# untitled.net
KiCad netlist of a schematic drawn in EAGLE
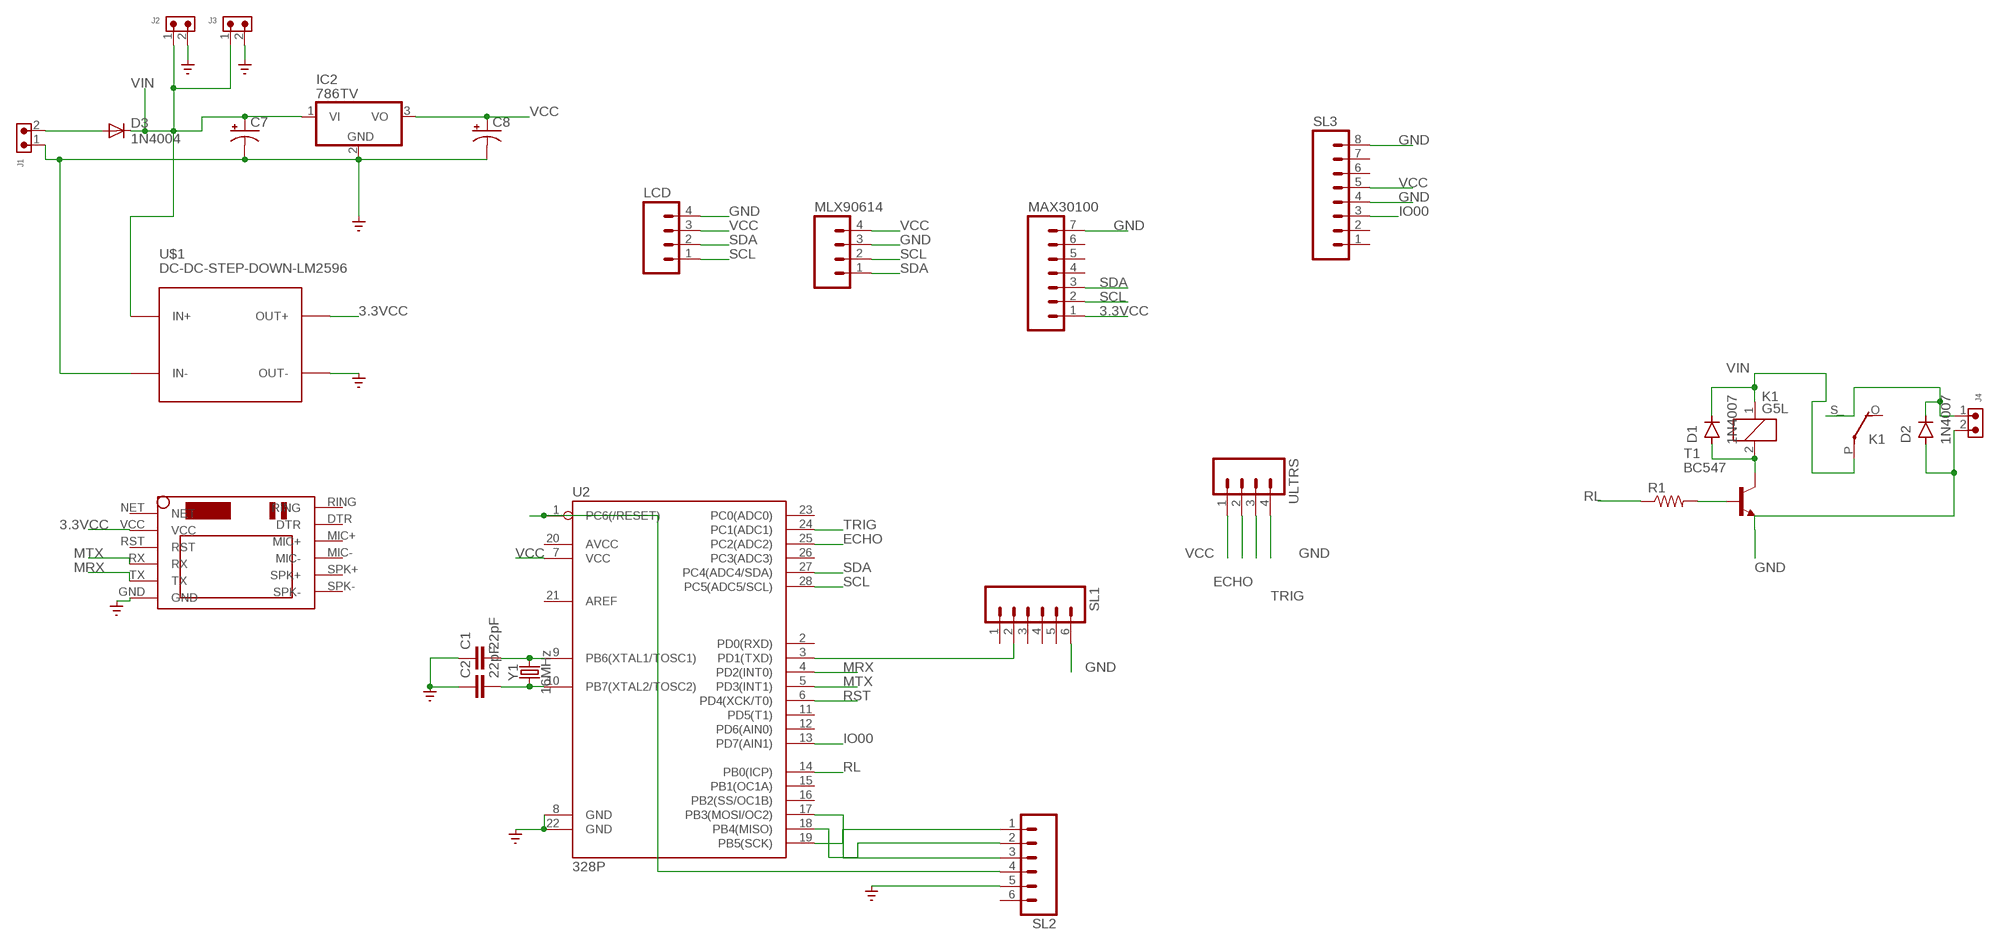
[diagram p0: schematic, sheet 1]

(export (version "E")
  (design (tool "Eeschema 10.0.6"))
  (components
    (comp (ref "C1")
      (value "22pF")
      (footprint "eagle-import:CAP-PTH-2.54")
      (libsource (lib "eagle-import") (part "22PF-PTH-2.54MM-200V-5%"))
    )
    (comp (ref "C2")
      (value "22pF")
      (footprint "eagle-import:CAP-PTH-2.54")
      (libsource (lib "eagle-import") (part "22PF-PTH-2.54MM-200V-5%"))
    )
    (comp (ref "C7")
      (value "CAPACITOR-PE5-10.5")
      (footprint "eagle-import:E5-10,5")
      (libsource (lib "eagle-import") (part "CAPACITOR-PE5-10.5"))
    )
    (comp (ref "C8")
      (value "CAPACITOR-PE5-6")
      (footprint "eagle-import:E5-6")
      (libsource (lib "eagle-import") (part "CAPACITOR-PE5-6"))
    )
    (comp (ref "D1")
      (value "1N4007")
      (footprint "eagle-import:DO-41")
      (fields
        (field (name "DIGIKEY_PART_NUMBER") "1N4007MSCT-ND")
        (field (name "MANUFACTURER") "Micro Commercial Co")
        (field (name "CREATED_BY") "PCBLayout.com")
      )
      (libsource (lib "eagle-import") (part "1N4007"))
    )
    (comp (ref "D2")
      (value "1N4007")
      (footprint "eagle-import:DO-41")
      (fields
        (field (name "DIGIKEY_PART_NUMBER") "1N4007MSCT-ND")
        (field (name "MANUFACTURER") "Micro Commercial Co")
        (field (name "CREATED_BY") "PCBLayout.com")
      )
      (libsource (lib "eagle-import") (part "1N4007"))
    )
    (comp (ref "D3")
      (value "1N4004")
      (footprint "eagle-import:DO41-10")
      (libsource (lib "eagle-import") (part "1N4004"))
    )
    (comp (ref "IC2")
      (value "786TV")
      (footprint "eagle-import:TO220V")
      (libsource (lib "eagle-import") (part "78TV6"))
    )
    (comp (ref "J1")
      (value "691305530002")
      (footprint "eagle-import:691305530002")
      (libsource (lib "eagle-import") (part "691305530002"))
    )
    (comp (ref "J2")
      (value "691305530002")
      (footprint "eagle-import:691305530002")
      (libsource (lib "eagle-import") (part "691305530002"))
    )
    (comp (ref "J3")
      (value "691305530002")
      (footprint "eagle-import:691305530002")
      (libsource (lib "eagle-import") (part "691305530002"))
    )
    (comp (ref "J4")
      (value "691305530002")
      (footprint "eagle-import:691305530002")
      (libsource (lib "eagle-import") (part "691305530002"))
    )
    (comp (ref "K1")
      (value "G5L")
      (footprint "eagle-import:G5LE")
      (libsource (lib "eagle-import") (part "G5L"))
    )
    (comp (ref "LCD")
      (value "M04")
      (footprint "eagle-import:04P")
      (libsource (lib "eagle-import") (part "M04"))
    )
    (comp (ref "MAX30100")
      (value "M07")
      (footprint "eagle-import:07P")
      (libsource (lib "eagle-import") (part "M07"))
    )
    (comp (ref "MLX90614")
      (value "M04")
      (footprint "eagle-import:04P")
      (libsource (lib "eagle-import") (part "M04"))
    )
    (comp (ref "R1")
      (value "R-US_0207/15")
      (footprint "eagle-import:0207_15")
      (libsource (lib "eagle-import") (part "R-US_0207/15"))
    )
    (comp (ref "SL1")
      (value "M06")
      (footprint "eagle-import:06P")
      (libsource (lib "eagle-import") (part "M06"))
    )
    (comp (ref "SL2")
      (value "M06")
      (footprint "eagle-import:06P")
      (libsource (lib "eagle-import") (part "M06"))
    )
    (comp (ref "SL3")
      (value "M08")
      (footprint "eagle-import:08P")
      (libsource (lib "eagle-import") (part "M08"))
    )
    (comp (ref "T1")
      (value "BC547")
      (footprint "eagle-import:TO92")
      (libsource (lib "eagle-import") (part "BC547"))
    )
    (comp (ref "U$1")
      (value "DC-DC-STEP-DOWN-LM2596")
      (footprint "eagle-import:DC-DC-STEP-DOWN-LM2596")
      (libsource (lib "eagle-import") (part "DC-DC-STEP-DOWN-LM2596"))
    )
    (comp (ref "U$2")
      (value "SIM800LMODULE")
      (footprint "eagle-import:SIM800LMODULE")
      (libsource (lib "eagle-import") (part "SIM800LMODULE"))
    )
    (comp (ref "U2")
      (value "328P")
      (footprint "eagle-import:DIP28")
      (libsource (lib "eagle-import") (part "ATMEGA328P_PDIP"))
    )
    (comp (ref "ULTRS")
      (value "M04")
      (footprint "eagle-import:04P")
      (libsource (lib "eagle-import") (part "M04"))
    )
    (comp (ref "Y1")
      (value "16MHz")
      (footprint "eagle-import:HC49US")
      (libsource (lib "eagle-import") (part "CRYSTAL-16MHZPTH-HC49US"))
    )
  )
  (nets
    (net (code "1") (name "/3.3VCC") (class "Default")
      (node (ref "MAX30100") (pin "1") (pinfunction "1_1") (pintype "passive"))
      (node (ref "U$1") (pin "OUT+") (pinfunction "OUT+_OUT+") (pintype "bidirectional"))
      (node (ref "U$2") (pin "VCC") (pinfunction "VCC_VCC") (pintype "bidirectional"))
    )
    (net (code "2") (name "/ECHO") (class "Default")
      (node (ref "U2") (pin "25") (pinfunction "PC2(ADC2)_25") (pintype "bidirectional"))
      (node (ref "ULTRS") (pin "2") (pinfunction "2_2") (pintype "passive"))
    )
    (net (code "3") (name "/IO00") (class "Default")
      (node (ref "SL3") (pin "3") (pinfunction "3_3") (pintype "passive"))
      (node (ref "U2") (pin "13") (pinfunction "PD7(AIN1)_13") (pintype "bidirectional"))
    )
    (net (code "4") (name "/MRX") (class "Default")
      (node (ref "U$2") (pin "TX") (pinfunction "TX_TX") (pintype "bidirectional"))
      (node (ref "U2") (pin "4") (pinfunction "PD2(INT0)_4") (pintype "bidirectional"))
    )
    (net (code "5") (name "/MTX") (class "Default")
      (node (ref "U$2") (pin "RX") (pinfunction "RX_RX") (pintype "bidirectional"))
      (node (ref "U2") (pin "5") (pinfunction "PD3(INT1)_5") (pintype "bidirectional"))
    )
    (net (code "6") (name "/RL") (class "Default")
      (node (ref "R1") (pin "1") (pinfunction "1_1") (pintype "passive"))
      (node (ref "U2") (pin "14") (pinfunction "PB0(ICP)_14") (pintype "bidirectional"))
    )
    (net (code "7") (name "/RST") (class "Default")
      (node (ref "U2") (pin "6") (pinfunction "PD4(XCK/T0)_6") (pintype "bidirectional"))
    )
    (net (code "8") (name "/SCL") (class "Default")
      (node (ref "LCD") (pin "1") (pinfunction "1_1") (pintype "passive"))
      (node (ref "MAX30100") (pin "2") (pinfunction "2_2") (pintype "passive"))
      (node (ref "MLX90614") (pin "2") (pinfunction "2_2") (pintype "passive"))
      (node (ref "U2") (pin "28") (pinfunction "PC5(ADC5/SCL)_28") (pintype "bidirectional"))
    )
    (net (code "9") (name "/SDA") (class "Default")
      (node (ref "LCD") (pin "2") (pinfunction "2_2") (pintype "passive"))
      (node (ref "MAX30100") (pin "3") (pinfunction "3_3") (pintype "passive"))
      (node (ref "MLX90614") (pin "1") (pinfunction "1_1") (pintype "passive"))
      (node (ref "U2") (pin "27") (pinfunction "PC4(ADC4/SDA)_27") (pintype "bidirectional"))
    )
    (net (code "10") (name "/TRIG") (class "Default")
      (node (ref "U2") (pin "24") (pinfunction "PC1(ADC1)_24") (pintype "bidirectional"))
      (node (ref "ULTRS") (pin "3") (pinfunction "3_3") (pintype "passive"))
    )
    (net (code "11") (name "/VCC") (class "Default")
      (node (ref "C8") (pin "+") (pinfunction "+_+") (pintype "passive"))
      (node (ref "IC2") (pin "3") (pinfunction "VO_3") (pintype "passive"))
      (node (ref "LCD") (pin "3") (pinfunction "3_3") (pintype "passive"))
      (node (ref "MLX90614") (pin "4") (pinfunction "4_4") (pintype "passive"))
      (node (ref "SL3") (pin "5") (pinfunction "5_5") (pintype "passive"))
      (node (ref "U2") (pin "7") (pinfunction "VCC_7") (pintype "bidirectional"))
      (node (ref "ULTRS") (pin "1") (pinfunction "1_1") (pintype "passive"))
    )
    (net (code "12") (name "/VIN") (class "Default")
      (node (ref "C7") (pin "+") (pinfunction "+_+") (pintype "passive"))
      (node (ref "D1") (pin "C") (pinfunction "C_C") (pintype "passive"))
      (node (ref "D3") (pin "C") (pinfunction "C_C") (pintype "passive"))
      (node (ref "IC2") (pin "1") (pinfunction "VI_1") (pintype "input"))
      (node (ref "J2") (pin "1") (pinfunction "1_1") (pintype "passive"))
      (node (ref "J3") (pin "1") (pinfunction "1_1") (pintype "passive"))
      (node (ref "K1") (pin "1") (pinfunction "1_1") (pintype "passive"))
      (node (ref "K1") (pin "P") (pinfunction "P_P") (pintype "passive"))
      (node (ref "U$1") (pin "IN+") (pinfunction "IN+_IN+") (pintype "bidirectional"))
    )
    (net (code "13") (name "Net-(D2-PadC)") (class "Default")
      (node (ref "D2") (pin "C") (pinfunction "C_C") (pintype "passive"))
      (node (ref "J4") (pin "1") (pinfunction "1_1") (pintype "passive"))
      (node (ref "K1") (pin "S") (pinfunction "S_S") (pintype "passive"))
    )
    (net (code "14") (name "Net-(D3-PadA)") (class "Default")
      (node (ref "D3") (pin "A") (pinfunction "A_A") (pintype "passive"))
      (node (ref "J1") (pin "2") (pinfunction "2_2") (pintype "passive"))
    )
    (net (code "15") (name "Net-(T1-B)") (class "Default")
      (node (ref "R1") (pin "2") (pinfunction "2_2") (pintype "passive"))
      (node (ref "T1") (pin "2") (pinfunction "B_2") (pintype "passive"))
    )
    (net (code "16") (name "Net-(T1-C)") (class "Default")
      (node (ref "D1") (pin "A") (pinfunction "A_A") (pintype "passive"))
      (node (ref "K1") (pin "2") (pinfunction "2_2") (pintype "passive"))
      (node (ref "T1") (pin "3") (pinfunction "C_3") (pintype "passive"))
    )
    (net (code "17") (name "Net-(U2-PB3(MOSI{slash}OC2))") (class "Default")
      (node (ref "SL2") (pin "3") (pinfunction "3_3") (pintype "passive"))
      (node (ref "U2") (pin "17") (pinfunction "PB3(MOSI/OC2)_17") (pintype "bidirectional"))
    )
    (net (code "18") (name "Net-(U2-PB4(MISO))") (class "Default")
      (node (ref "SL2") (pin "2") (pinfunction "2_2") (pintype "passive"))
      (node (ref "U2") (pin "18") (pinfunction "PB4(MISO)_18") (pintype "bidirectional"))
    )
    (net (code "19") (name "Net-(U2-PB5(SCK))") (class "Default")
      (node (ref "SL2") (pin "1") (pinfunction "1_1") (pintype "passive"))
      (node (ref "U2") (pin "19") (pinfunction "PB5(SCK)_19") (pintype "bidirectional"))
    )
    (net (code "20") (name "Net-(U2-PB6(XTAL1{slash}TOSC1))") (class "Default")
      (node (ref "C1") (pin "2") (pinfunction "2_2") (pintype "passive"))
      (node (ref "U2") (pin "9") (pinfunction "PB6(XTAL1/TOSC1)_9") (pintype "bidirectional"))
      (node (ref "Y1") (pin "2") (pinfunction "2_2") (pintype "passive"))
    )
    (net (code "21") (name "Net-(U2-PB7(XTAL2{slash}TOSC2))") (class "Default")
      (node (ref "C2") (pin "2") (pinfunction "2_2") (pintype "passive"))
      (node (ref "U2") (pin "10") (pinfunction "PB7(XTAL2/TOSC2)_10") (pintype "bidirectional"))
      (node (ref "Y1") (pin "1") (pinfunction "1_1") (pintype "passive"))
    )
    (net (code "22") (name "Net-(U2-PC6({slash}RESET))") (class "Default")
      (node (ref "SL2") (pin "4") (pinfunction "4_4") (pintype "passive"))
      (node (ref "U2") (pin "1") (pinfunction "PC6(/RESET)_1") (pintype "bidirectional"))
    )
    (net (code "23") (name "Net-(U2-PD1(TXD))") (class "Default")
      (node (ref "SL1") (pin "2") (pinfunction "2_2") (pintype "passive"))
      (node (ref "U2") (pin "3") (pinfunction "PD1(TXD)_3") (pintype "bidirectional"))
    )
    (net (code "24") (name "SUPPLY_BRASTAN_GND_") (class "Default")
      (node (ref "C1") (pin "1") (pinfunction "1_1") (pintype "passive"))
      (node (ref "C2") (pin "1") (pinfunction "1_1") (pintype "passive"))
      (node (ref "C7") (pin "-") (pinfunction "-_-") (pintype "passive"))
      (node (ref "C8") (pin "-") (pinfunction "-_-") (pintype "passive"))
      (node (ref "D2") (pin "A") (pinfunction "A_A") (pintype "passive"))
      (node (ref "IC2") (pin "2") (pinfunction "GND_2") (pintype "passive"))
      (node (ref "J1") (pin "1") (pinfunction "1_1") (pintype "passive"))
      (node (ref "J2") (pin "2") (pinfunction "2_2") (pintype "passive"))
      (node (ref "J3") (pin "2") (pinfunction "2_2") (pintype "passive"))
      (node (ref "J4") (pin "2") (pinfunction "2_2") (pintype "passive"))
      (node (ref "LCD") (pin "4") (pinfunction "4_4") (pintype "passive"))
      (node (ref "MAX30100") (pin "7") (pinfunction "7_7") (pintype "passive"))
      (node (ref "MLX90614") (pin "3") (pinfunction "3_3") (pintype "passive"))
      (node (ref "SL1") (pin "6") (pinfunction "6_6") (pintype "passive"))
      (node (ref "SL2") (pin "5") (pinfunction "5_5") (pintype "passive"))
      (node (ref "SL3") (pin "4") (pinfunction "4_4") (pintype "passive"))
      (node (ref "SL3") (pin "8") (pinfunction "8_8") (pintype "passive"))
      (node (ref "T1") (pin "1") (pinfunction "E_1") (pintype "passive"))
      (node (ref "U$1") (pin "IN-") (pinfunction "IN-_IN-") (pintype "bidirectional"))
      (node (ref "U$1") (pin "OUT-") (pinfunction "OUT-_OUT-") (pintype "bidirectional"))
      (node (ref "U$2") (pin "GND") (pinfunction "GND_GND") (pintype "bidirectional"))
      (node (ref "U2") (pin "22") (pinfunction "GND_22") (pintype "bidirectional"))
      (node (ref "U2") (pin "8") (pinfunction "GND_8") (pintype "bidirectional"))
      (node (ref "ULTRS") (pin "4") (pinfunction "4_4") (pintype "passive"))
    )
    (net (code "25") (name "unconnected-(K1-PadO)") (class "Default")
      (node (ref "K1") (pin "O") (pinfunction "O_O") (pintype "passive"))
    )
    (net (code "26") (name "unconnected-(MAX30100-Pad4)") (class "Default")
      (node (ref "MAX30100") (pin "4") (pinfunction "4_4") (pintype "passive"))
    )
    (net (code "27") (name "unconnected-(MAX30100-Pad5)") (class "Default")
      (node (ref "MAX30100") (pin "5") (pinfunction "5_5") (pintype "passive"))
    )
    (net (code "28") (name "unconnected-(MAX30100-Pad6)") (class "Default")
      (node (ref "MAX30100") (pin "6") (pinfunction "6_6") (pintype "passive"))
    )
    (net (code "29") (name "unconnected-(SL1-Pad1)") (class "Default")
      (node (ref "SL1") (pin "1") (pinfunction "1_1") (pintype "passive"))
    )
    (net (code "30") (name "unconnected-(SL1-Pad3)") (class "Default")
      (node (ref "SL1") (pin "3") (pinfunction "3_3") (pintype "passive"))
    )
    (net (code "31") (name "unconnected-(SL1-Pad4)") (class "Default")
      (node (ref "SL1") (pin "4") (pinfunction "4_4") (pintype "passive"))
    )
    (net (code "32") (name "unconnected-(SL1-Pad5)") (class "Default")
      (node (ref "SL1") (pin "5") (pinfunction "5_5") (pintype "passive"))
    )
    (net (code "33") (name "unconnected-(SL2-Pad6)") (class "Default")
      (node (ref "SL2") (pin "6") (pinfunction "6_6") (pintype "passive"))
    )
    (net (code "34") (name "unconnected-(SL3-Pad1)") (class "Default")
      (node (ref "SL3") (pin "1") (pinfunction "1_1") (pintype "passive"))
    )
    (net (code "35") (name "unconnected-(SL3-Pad2)") (class "Default")
      (node (ref "SL3") (pin "2") (pinfunction "2_2") (pintype "passive"))
    )
    (net (code "36") (name "unconnected-(SL3-Pad6)") (class "Default")
      (node (ref "SL3") (pin "6") (pinfunction "6_6") (pintype "passive"))
    )
    (net (code "37") (name "unconnected-(SL3-Pad7)") (class "Default")
      (node (ref "SL3") (pin "7") (pinfunction "7_7") (pintype "passive"))
    )
    (net (code "38") (name "unconnected-(U$2-PadDTR)") (class "Default")
      (node (ref "U$2") (pin "DTR") (pinfunction "DTR_DTR") (pintype "bidirectional"))
    )
    (net (code "39") (name "unconnected-(U$2-PadMIC+)") (class "Default")
      (node (ref "U$2") (pin "MIC+") (pinfunction "MIC+_MIC+") (pintype "bidirectional"))
    )
    (net (code "40") (name "unconnected-(U$2-PadMIC-)") (class "Default")
      (node (ref "U$2") (pin "MIC-") (pinfunction "MIC-_MIC-") (pintype "bidirectional"))
    )
    (net (code "41") (name "unconnected-(U$2-PadNET)") (class "Default")
      (node (ref "U$2") (pin "NET") (pinfunction "NET_NET") (pintype "bidirectional"))
    )
    (net (code "42") (name "unconnected-(U$2-PadRING)") (class "Default")
      (node (ref "U$2") (pin "RING") (pinfunction "RING_RING") (pintype "bidirectional"))
    )
    (net (code "43") (name "unconnected-(U$2-PadRST)") (class "Default")
      (node (ref "U$2") (pin "RST") (pinfunction "RST_RST") (pintype "bidirectional"))
    )
    (net (code "44") (name "unconnected-(U$2-PadSPK+)") (class "Default")
      (node (ref "U$2") (pin "SPK+") (pinfunction "SPK+_SPK+") (pintype "bidirectional"))
    )
    (net (code "45") (name "unconnected-(U$2-PadSPK-)") (class "Default")
      (node (ref "U$2") (pin "SPK-") (pinfunction "SPK-_SPK-") (pintype "bidirectional"))
    )
    (net (code "46") (name "unconnected-(U2-AREF-Pad21)") (class "Default")
      (node (ref "U2") (pin "21") (pinfunction "AREF_21") (pintype "bidirectional"))
    )
    (net (code "47") (name "unconnected-(U2-AVCC-Pad20)") (class "Default")
      (node (ref "U2") (pin "20") (pinfunction "AVCC_20") (pintype "bidirectional"))
    )
    (net (code "48") (name "unconnected-(U2-PB1(OC1A)-Pad15)") (class "Default")
      (node (ref "U2") (pin "15") (pinfunction "PB1(OC1A)_15") (pintype "bidirectional"))
    )
    (net (code "49") (name "unconnected-(U2-PB2(SS{slash}OC1B)-Pad16)") (class "Default")
      (node (ref "U2") (pin "16") (pinfunction "PB2(SS/OC1B)_16") (pintype "bidirectional"))
    )
    (net (code "50") (name "unconnected-(U2-PC0(ADC0)-Pad23)") (class "Default")
      (node (ref "U2") (pin "23") (pinfunction "PC0(ADC0)_23") (pintype "bidirectional"))
    )
    (net (code "51") (name "unconnected-(U2-PC3(ADC3)-Pad26)") (class "Default")
      (node (ref "U2") (pin "26") (pinfunction "PC3(ADC3)_26") (pintype "bidirectional"))
    )
    (net (code "52") (name "unconnected-(U2-PD0(RXD)-Pad2)") (class "Default")
      (node (ref "U2") (pin "2") (pinfunction "PD0(RXD)_2") (pintype "bidirectional"))
    )
    (net (code "53") (name "unconnected-(U2-PD5(T1)-Pad11)") (class "Default")
      (node (ref "U2") (pin "11") (pinfunction "PD5(T1)_11") (pintype "bidirectional"))
    )
    (net (code "54") (name "unconnected-(U2-PD6(AIN0)-Pad12)") (class "Default")
      (node (ref "U2") (pin "12") (pinfunction "PD6(AIN0)_12") (pintype "bidirectional"))
    )
  )
)
